# Helepolis_Level2.net
KiCad netlist of a schematic drawn in EAGLE
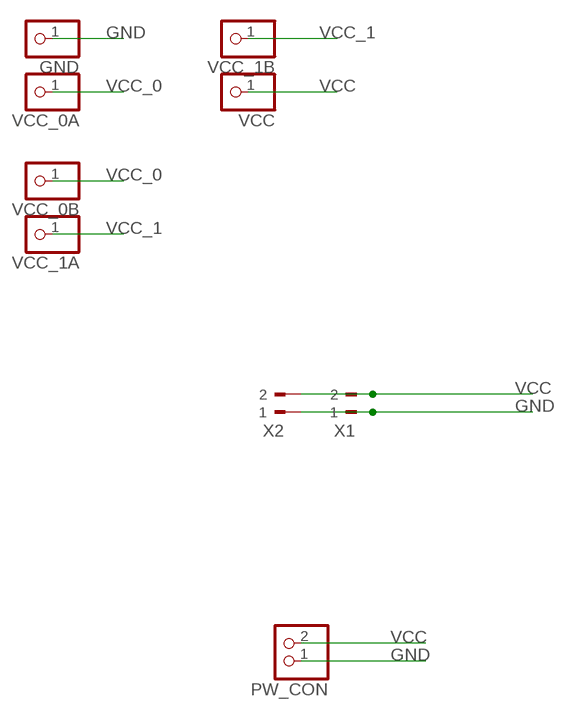
[diagram p0: schematic, sheet 1]

(export (version "E")
  (design (tool "Eeschema 10.0.6"))
  (components
    (comp (ref "GND")
      (value "PINHD-1X1")
      (footprint "eagle-import:1X01")
      (libsource (lib "eagle-import") (part "PINHD-1X1"))
    )
    (comp (ref "PW_CON")
      (value "PINHD-1X2")
      (footprint "eagle-import:1X02")
      (libsource (lib "eagle-import") (part "PINHD-1X2"))
    )
    (comp (ref "VCC")
      (value "PINHD-1X1")
      (footprint "eagle-import:1X01")
      (libsource (lib "eagle-import") (part "PINHD-1X1"))
    )
    (comp (ref "VCC_0A")
      (value "PINHD-1X1")
      (footprint "eagle-import:1X01")
      (libsource (lib "eagle-import") (part "PINHD-1X1"))
    )
    (comp (ref "VCC_0B")
      (value "PINHD-1X1")
      (footprint "eagle-import:1X01")
      (libsource (lib "eagle-import") (part "PINHD-1X1"))
    )
    (comp (ref "VCC_1A")
      (value "PINHD-1X1")
      (footprint "eagle-import:1X01")
      (libsource (lib "eagle-import") (part "PINHD-1X1"))
    )
    (comp (ref "VCC_1B")
      (value "PINHD-1X1")
      (footprint "eagle-import:1X01")
      (libsource (lib "eagle-import") (part "PINHD-1X1"))
    )
    (comp (ref "X1")
      (value "90-2")
      (footprint "eagle-import:90-2")
      (libsource (lib "eagle-import") (part "90-2"))
    )
    (comp (ref "X2")
      (value "90-2")
      (footprint "eagle-import:90-2")
      (libsource (lib "eagle-import") (part "90-2"))
    )
  )
  (nets
    (net (code "1") (name "/GND") (class "Default")
      (node (ref "GND") (pin "1") (pinfunction "1_1") (pintype "passive"))
      (node (ref "PW_CON") (pin "1") (pinfunction "1_1") (pintype "passive"))
      (node (ref "X1") (pin "1") (pinfunction "1_1") (pintype "passive"))
      (node (ref "X2") (pin "1") (pinfunction "1_1") (pintype "passive"))
    )
    (net (code "2") (name "/VCC") (class "Default")
      (node (ref "PW_CON") (pin "2") (pinfunction "2_2") (pintype "passive"))
      (node (ref "VCC") (pin "1") (pinfunction "1_1") (pintype "passive"))
      (node (ref "X1") (pin "2") (pinfunction "2_2") (pintype "passive"))
      (node (ref "X2") (pin "2") (pinfunction "2_2") (pintype "passive"))
    )
    (net (code "3") (name "/VCC_0") (class "Default")
      (node (ref "VCC_0A") (pin "1") (pinfunction "1_1") (pintype "passive"))
      (node (ref "VCC_0B") (pin "1") (pinfunction "1_1") (pintype "passive"))
    )
    (net (code "4") (name "/VCC_1") (class "Default")
      (node (ref "VCC_1A") (pin "1") (pinfunction "1_1") (pintype "passive"))
      (node (ref "VCC_1B") (pin "1") (pinfunction "1_1") (pintype "passive"))
    )
  )
)
